# lab_1_zasetskiy_usb_spi.net
KiCad netlist of a schematic drawn in Altium Designer
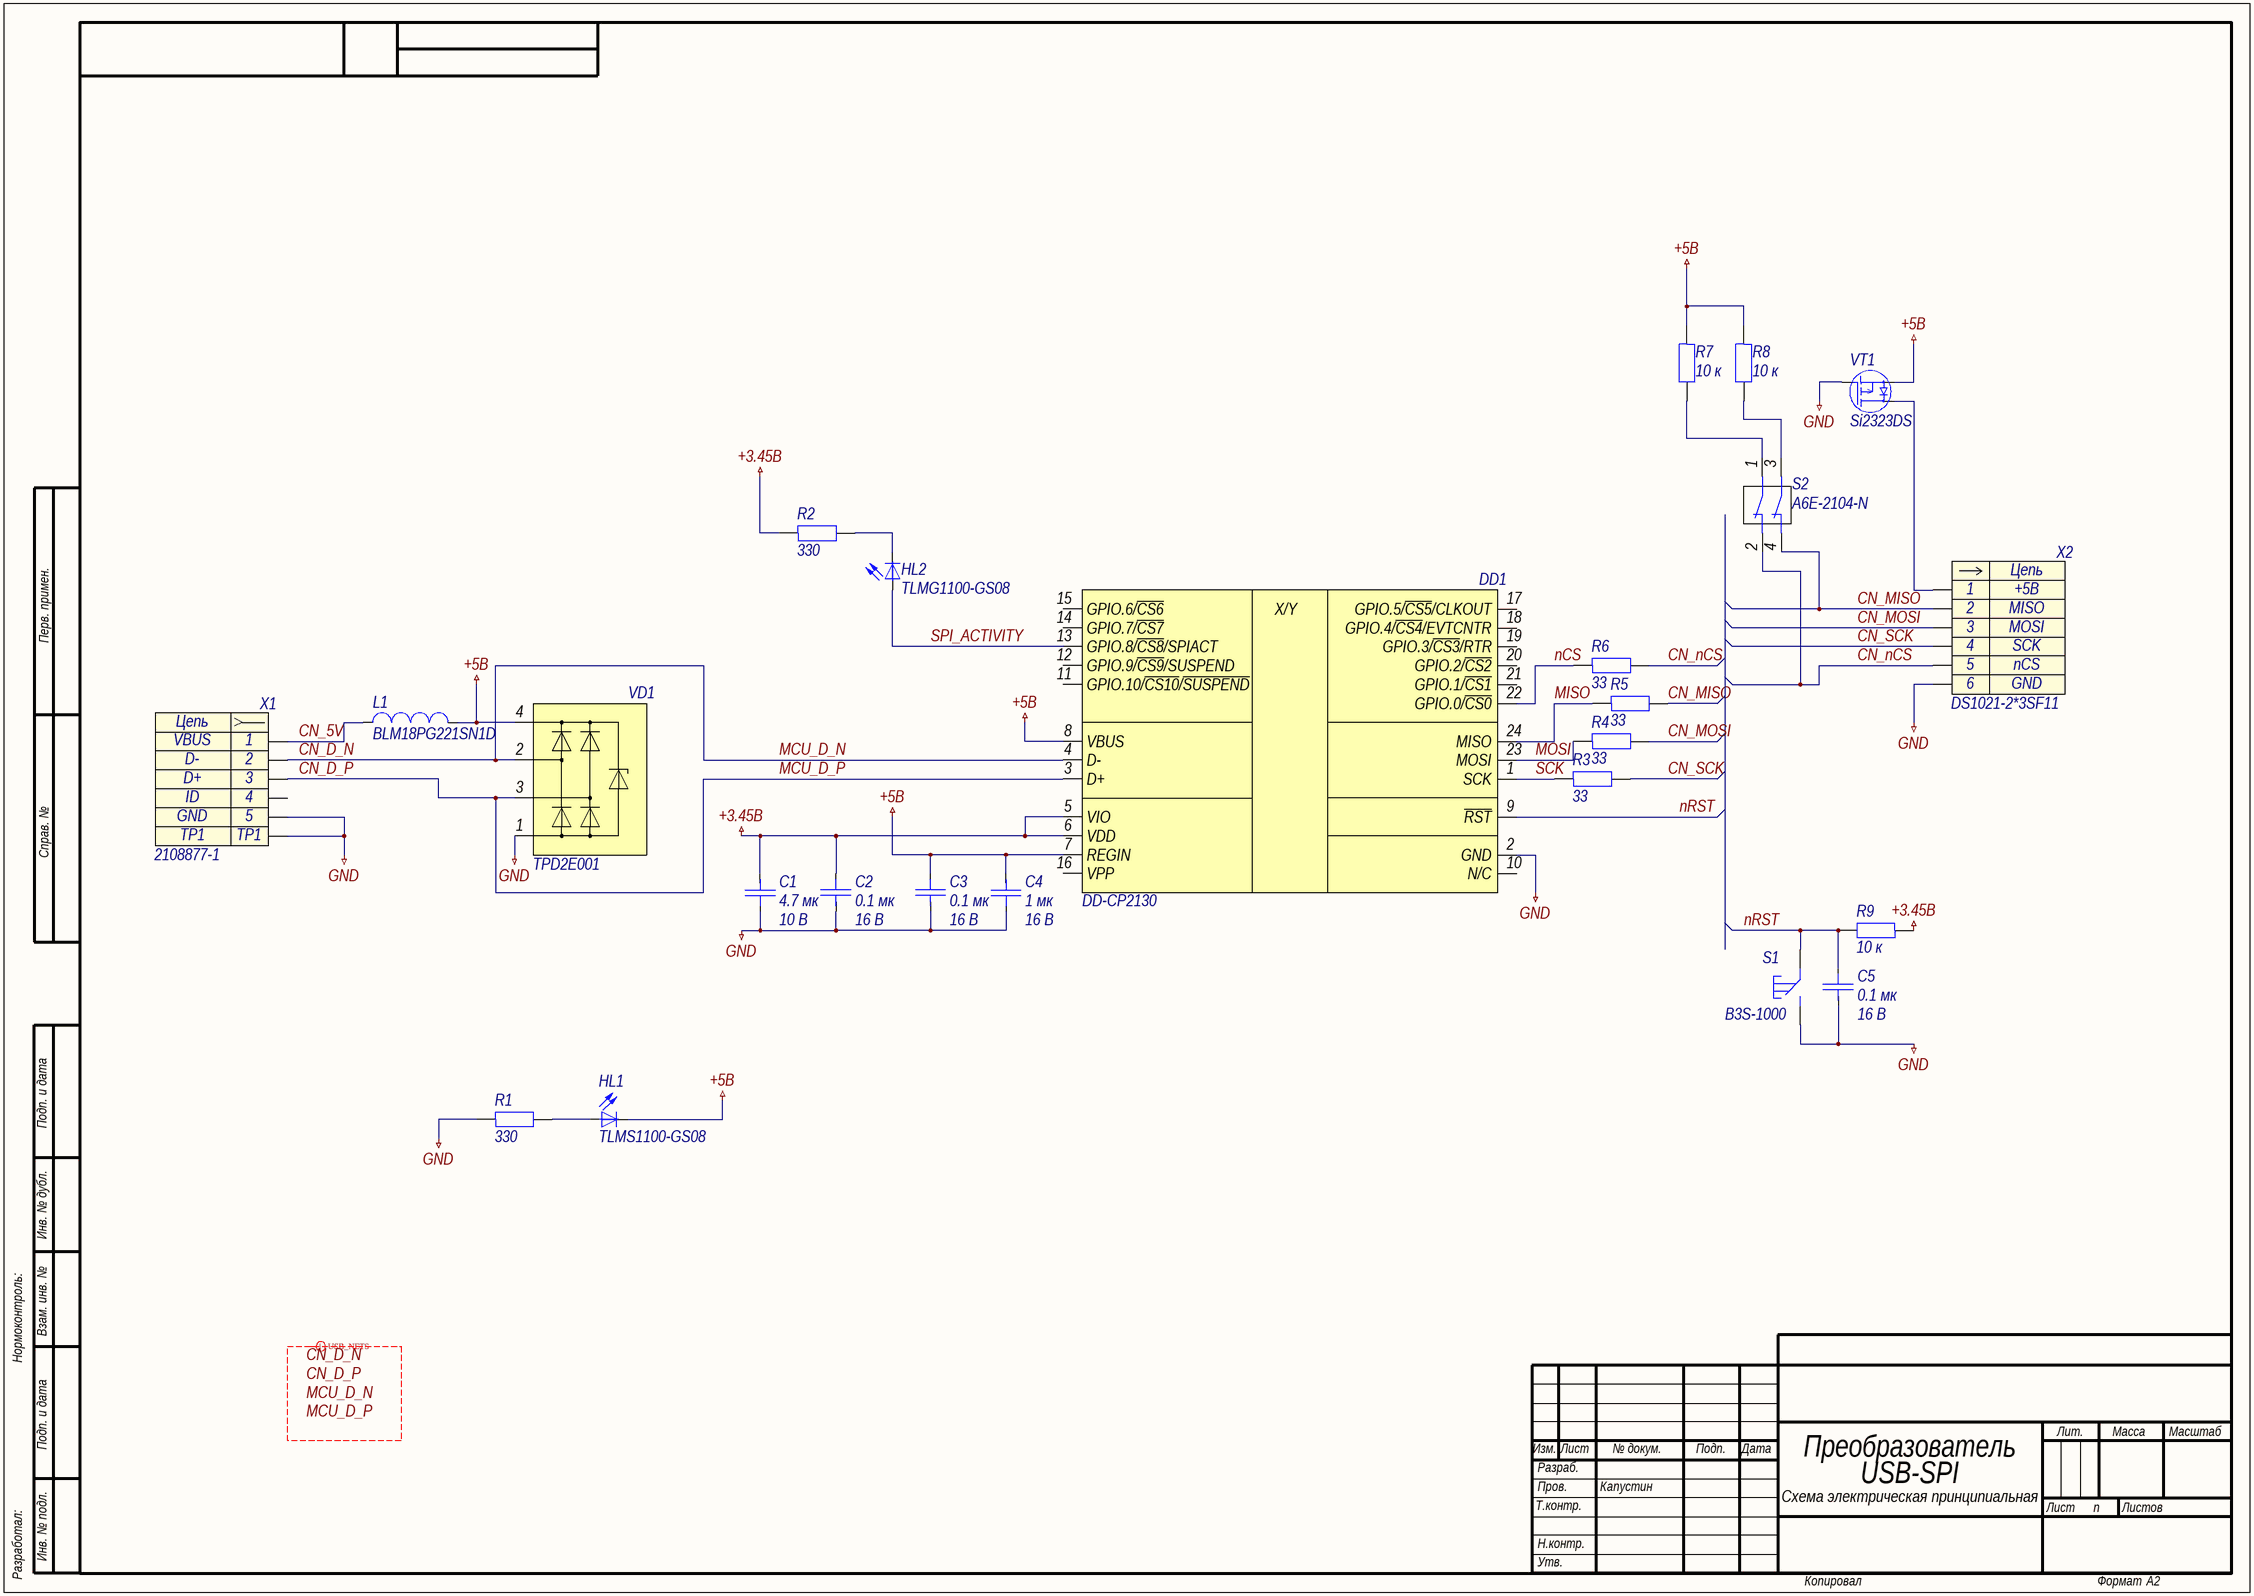
[diagram p0: lab_1_zasetskiy_usb_spi.SchDoc]

(export (version "E")
  (design (tool "Eeschema 10.0.6"))
  (components
    (comp (ref "C1")
      (value "4.7 мк")
      (footprint "C0402")
      (description "=Описание")
      (fields (field (name "НАПРЯЖЕНИЕ") "10 В"))
      (libsource (lib "Database_Students") (part "cap"))
    )
    (comp (ref "C2")
      (value "0.1 мк")
      (footprint "C0402")
      (description "=Описание")
      (fields (field (name "НАПРЯЖЕНИЕ") "16 В"))
      (libsource (lib "Database_Students") (part "cap"))
    )
    (comp (ref "C3")
      (value "0.1 мк")
      (footprint "C0402")
      (description "=Описание")
      (fields (field (name "НАПРЯЖЕНИЕ") "16 В"))
      (libsource (lib "Database_Students") (part "cap"))
    )
    (comp (ref "C4")
      (value "1 мк")
      (footprint "C0402")
      (description "=Описание")
      (fields (field (name "НАПРЯЖЕНИЕ") "16 В"))
      (libsource (lib "Database_Students") (part "cap"))
    )
    (comp (ref "C5")
      (value "0.1 мк")
      (footprint "C0402")
      (description "=Описание")
      (fields (field (name "НАПРЯЖЕНИЕ") "16 В"))
      (libsource (lib "Database_Students") (part "cap"))
    )
    (comp (ref "DD1")
      (value "DD-CP2130")
      (footprint "CP2130")
      (description "=Описание")
      (libsource (lib "Database_Students") (part "DD-CP2130"))
    )
    (comp (ref "HL1")
      (value "TLMS1100-GS08")
      (footprint "LED")
      (description "=Описание")
      (libsource (lib "Database_Students") (part "led"))
    )
    (comp (ref "HL2")
      (value "TLMG1100-GS08")
      (footprint "LED_GREEN")
      (description "=Описание")
      (libsource (lib "Database_Students") (part "led"))
    )
    (comp (ref "L1")
      (value "BLM18PG221SN1D")
      (footprint "L0603")
      (description "=Описание")
      (libsource (lib "Database_Students") (part "L-bead"))
    )
    (comp (ref "R1")
      (value "330")
      (footprint "R0603")
      (description "=Описание")
      (libsource (lib "Database_Students") (part "R-0.063W"))
    )
    (comp (ref "R2")
      (value "330")
      (footprint "R0603")
      (description "=Описание")
      (libsource (lib "Database_Students") (part "R-0.063W"))
    )
    (comp (ref "R3")
      (value "33")
      (footprint "R0603")
      (description "=Описание")
      (libsource (lib "Database_Students") (part "R-0.063W"))
    )
    (comp (ref "R4")
      (value "33")
      (footprint "R0603")
      (description "=Описание")
      (libsource (lib "Database_Students") (part "R-0.063W"))
    )
    (comp (ref "R5")
      (value "33")
      (footprint "R0603")
      (description "=Описание")
      (libsource (lib "Database_Students") (part "R-0.063W"))
    )
    (comp (ref "R6")
      (value "33")
      (footprint "R0603")
      (description "=Описание")
      (libsource (lib "Database_Students") (part "R-0.063W"))
    )
    (comp (ref "R7")
      (value "10 к")
      (footprint "R0603")
      (description "=Описание")
      (libsource (lib "Database_Students") (part "R-0.063W"))
    )
    (comp (ref "R8")
      (value "10 к")
      (footprint "R0603")
      (description "=Описание")
      (libsource (lib "Database_Students") (part "R-0.063W"))
    )
    (comp (ref "R9")
      (value "10 к")
      (footprint "R0603")
      (description "=Описание")
      (libsource (lib "Database_Students") (part "R-0.063W"))
    )
    (comp (ref "S1")
      (value "B3S-1000")
      (footprint "BUTTON")
      (description "=Описание")
      (libsource (lib "Database_Students") (part "S-button"))
    )
    (comp (ref "S2")
      (value "A6E-2104-N")
      (footprint "A6E-2104-N")
      (description "=Описание")
      (libsource (lib "Database_Students") (part "switch"))
    )
    (comp (ref "VD1")
      (value "TPD2E001")
      (footprint "SOP")
      (libsource (lib "Database_Students") (part "tpd2e001"))
    )
    (comp (ref "VT1")
      (value "Si2323DS")
      (footprint "VT-SOT23")
      (description "=Описание")
      (libsource (lib "Database_Students") (part "P-channel_MOSFET"))
    )
    (comp (ref "X1")
      (value "2108877-1")
      (footprint "2108877-1")
      (description "=Описание")
      (libsource (lib "Database_Students") (part "MICRO_USB-B"))
    )
    (comp (ref "X2")
      (value "DS1021-2*3SF11")
      (footprint "PLS_2.54_2x3")
      (description "=Описание")
      (libsource (lib "Database_Students") (part "DS1021-2*3SF11"))
    )
  )
  (nets
    (net (code "1") (name "+3.45В") (class "Default")
      (node (ref "C1") (pin "2") (pinfunction "2_2") (pintype "passive"))
      (node (ref "C2") (pin "1") (pinfunction "1_1") (pintype "passive"))
      (node (ref "DD1") (pin "5") (pinfunction "VIO_5") (pintype "passive"))
      (node (ref "DD1") (pin "6") (pinfunction "VDD_6") (pintype "passive"))
      (node (ref "R2") (pin "1") (pinfunction "1_1") (pintype "passive"))
      (node (ref "R9") (pin "1") (pinfunction "1_1") (pintype "passive"))
    )
    (net (code "2") (name "+5В") (class "Default")
      (node (ref "C3") (pin "1") (pinfunction "1_1") (pintype "passive"))
      (node (ref "C4") (pin "2") (pinfunction "2_2") (pintype "passive"))
      (node (ref "DD1") (pin "7") (pinfunction "REGIN_7") (pintype "passive"))
      (node (ref "DD1") (pin "8") (pinfunction "VBUS_8") (pintype "passive"))
      (node (ref "HL1") (pin "2") (pinfunction "K_2") (pintype "passive"))
      (node (ref "L1") (pin "2") (pinfunction "2_2") (pintype "passive"))
      (node (ref "R7") (pin "1") (pinfunction "1_1") (pintype "passive"))
      (node (ref "R8") (pin "1") (pinfunction "1_1") (pintype "passive"))
      (node (ref "VD1") (pin "4") (pintype "passive"))
      (node (ref "VT1") (pin "3") (pinfunction "3_3") (pintype "passive"))
    )
    (net (code "3") (name "/CN_5V") (class "Default")
      (node (ref "L1") (pin "1") (pinfunction "1_1") (pintype "passive"))
      (node (ref "X1") (pin "1") (pinfunction "1_1") (pintype "passive"))
    )
    (net (code "4") (name "/CN_D_N") (class "Default")
      (node (ref "DD1") (pin "4") (pinfunction "D-_4") (pintype "passive"))
      (node (ref "VD1") (pin "2") (pintype "passive"))
      (node (ref "X1") (pin "2") (pinfunction "2_2") (pintype "passive"))
    )
    (net (code "5") (name "/CN_D_P") (class "Default")
      (node (ref "DD1") (pin "3") (pinfunction "D+_3") (pintype "passive"))
      (node (ref "VD1") (pin "3") (pintype "passive"))
      (node (ref "X1") (pin "3") (pinfunction "3_3") (pintype "passive"))
    )
    (net (code "6") (name "/CN_MISO") (class "Default")
      (node (ref "R5") (pin "2") (pinfunction "2_2") (pintype "passive"))
      (node (ref "S2") (pin "4") (pinfunction "4_4") (pintype "passive"))
      (node (ref "X2") (pin "2") (pinfunction "2_2") (pintype "passive"))
    )
    (net (code "7") (name "/CN_MOSI") (class "Default")
      (node (ref "R4") (pin "2") (pinfunction "2_2") (pintype "passive"))
      (node (ref "X2") (pin "3") (pinfunction "3_3") (pintype "passive"))
    )
    (net (code "8") (name "/CN_SCK") (class "Default")
      (node (ref "R3") (pin "2") (pinfunction "2_2") (pintype "passive"))
      (node (ref "X2") (pin "4") (pinfunction "4_4") (pintype "passive"))
    )
    (net (code "9") (name "/CN_nCS") (class "Default")
      (node (ref "R6") (pin "2") (pinfunction "2_2") (pintype "passive"))
      (node (ref "S2") (pin "2") (pinfunction "2_2") (pintype "passive"))
      (node (ref "X2") (pin "5") (pinfunction "5_5") (pintype "passive"))
    )
    (net (code "10") (name "/MISO") (class "Default")
      (node (ref "DD1") (pin "24") (pinfunction "MISO_24") (pintype "passive"))
      (node (ref "R5") (pin "1") (pinfunction "1_1") (pintype "passive"))
    )
    (net (code "11") (name "/MOSI") (class "Default")
      (node (ref "DD1") (pin "23") (pinfunction "MOSI_23") (pintype "passive"))
      (node (ref "R4") (pin "1") (pinfunction "1_1") (pintype "passive"))
    )
    (net (code "12") (name "/SCK") (class "Default")
      (node (ref "DD1") (pin "1") (pinfunction "SCK_1") (pintype "passive"))
      (node (ref "R3") (pin "1") (pinfunction "1_1") (pintype "passive"))
    )
    (net (code "13") (name "/SPI_ACTIVITY") (class "Default")
      (node (ref "DD1") (pin "13") (pinfunction "GPIO.8/~{CS8}/SPIACT_13") (pintype "passive"))
      (node (ref "HL2") (pin "1") (pinfunction "A_1") (pintype "passive"))
    )
    (net (code "14") (name "/nCS") (class "Default")
      (node (ref "DD1") (pin "22") (pinfunction "GPIO.0/~{CS0}_22") (pintype "passive"))
      (node (ref "R6") (pin "1") (pinfunction "1_1") (pintype "passive"))
    )
    (net (code "15") (name "/nRST") (class "Default")
      (node (ref "C5") (pin "1") (pinfunction "1_1") (pintype "passive"))
      (node (ref "DD1") (pin "9") (pinfunction "~{RST}_9") (pintype "passive"))
      (node (ref "R9") (pin "2") (pinfunction "2_2") (pintype "passive"))
      (node (ref "S1") (pin "2") (pinfunction "2_2") (pintype "passive"))
    )
    (net (code "16") (name "GND") (class "Default")
      (node (ref "C1") (pin "1") (pinfunction "1_1") (pintype "passive"))
      (node (ref "C2") (pin "2") (pinfunction "2_2") (pintype "passive"))
      (node (ref "C3") (pin "2") (pinfunction "2_2") (pintype "passive"))
      (node (ref "C4") (pin "1") (pinfunction "1_1") (pintype "passive"))
      (node (ref "C5") (pin "2") (pinfunction "2_2") (pintype "passive"))
      (node (ref "DD1") (pin "2") (pinfunction "GND_2") (pintype "passive"))
      (node (ref "R1") (pin "1") (pinfunction "1_1") (pintype "passive"))
      (node (ref "VD1") (pin "1") (pintype "passive"))
      (node (ref "X1") (pin "5") (pinfunction "5_5") (pintype "passive"))
      (node (ref "X1") (pin "TP1") (pinfunction "TP1_TP1") (pintype "passive"))
      (node (ref "X2") (pin "6") (pinfunction "6_6") (pintype "passive"))
    )
    (net (code "17") (name "Net-(HL1-A)") (class "Default")
      (node (ref "HL1") (pin "1") (pinfunction "A_1") (pintype "passive"))
      (node (ref "R1") (pin "2") (pinfunction "2_2") (pintype "passive"))
    )
    (net (code "18") (name "Net-(HL2-K)") (class "Default")
      (node (ref "HL2") (pin "2") (pinfunction "K_2") (pintype "passive"))
      (node (ref "R2") (pin "2") (pinfunction "2_2") (pintype "passive"))
    )
    (net (code "19") (name "Net-(R7-Pad2)") (class "Default")
      (node (ref "R7") (pin "2") (pinfunction "2_2") (pintype "passive"))
      (node (ref "S2") (pin "1") (pinfunction "1_1") (pintype "passive"))
    )
    (net (code "20") (name "Net-(R8-Pad2)") (class "Default")
      (node (ref "R8") (pin "2") (pinfunction "2_2") (pintype "passive"))
      (node (ref "S2") (pin "3") (pinfunction "3_3") (pintype "passive"))
    )
    (net (code "21") (name "Net-(VT1-Pad2)") (class "Default")
      (node (ref "VT1") (pin "2") (pinfunction "2_2") (pintype "passive"))
      (node (ref "X2") (pin "1") (pinfunction "1_1") (pintype "passive"))
    )
    (net (code "22") (name "unconnected-(DD1-GPIO.1{slash}~{CS1}-Pad21)") (class "Default")
      (node (ref "DD1") (pin "21") (pinfunction "GPIO.1/~{CS1}_21") (pintype "passive"))
    )
    (net (code "23") (name "unconnected-(DD1-GPIO.2{slash}~{CS2}-Pad20)") (class "Default")
      (node (ref "DD1") (pin "20") (pinfunction "GPIO.2/~{CS2}_20") (pintype "passive"))
    )
    (net (code "24") (name "unconnected-(DD1-GPIO.3{slash}~{CS3}{slash}RTR-Pad19)") (class "Default")
      (node (ref "DD1") (pin "19") (pinfunction "GPIO.3/~{CS3}/RTR_19") (pintype "passive"))
    )
    (net (code "25") (name "unconnected-(DD1-GPIO.4{slash}~{CS4}{slash}EVTCNTR-Pad18)") (class "Default")
      (node (ref "DD1") (pin "18") (pinfunction "GPIO.4/~{CS4}/EVTCNTR_18") (pintype "passive"))
    )
    (net (code "26") (name "unconnected-(DD1-GPIO.5{slash}~{CS5}{slash}CLKOUT-Pad17)") (class "Default")
      (node (ref "DD1") (pin "17") (pinfunction "GPIO.5/~{CS5}/CLKOUT_17") (pintype "passive"))
    )
    (net (code "27") (name "unconnected-(DD1-GPIO.6{slash}~{CS6}-Pad15)") (class "Default")
      (node (ref "DD1") (pin "15") (pinfunction "GPIO.6/~{CS6}_15") (pintype "passive"))
    )
    (net (code "28") (name "unconnected-(DD1-GPIO.7{slash}~{CS7}-Pad14)") (class "Default")
      (node (ref "DD1") (pin "14") (pinfunction "GPIO.7/~{CS7}_14") (pintype "passive"))
    )
    (net (code "29") (name "unconnected-(DD1-GPIO.9{slash}~{CS9}{slash}SUSPEND-Pad12)") (class "Default")
      (node (ref "DD1") (pin "12") (pinfunction "GPIO.9/~{CS9}/SUSPEND_12") (pintype "passive"))
    )
    (net (code "30") (name "unconnected-(DD1-GPIO.10{slash}~{CS10}{slash}~{SUSPEND}-Pad11)") (class "Default")
      (node (ref "DD1") (pin "11") (pinfunction "GPIO.10/~{CS10}/~{SUSPEND}_11") (pintype "passive"))
    )
    (net (code "31") (name "unconnected-(DD1-N{slash}C-Pad10)") (class "Default")
      (node (ref "DD1") (pin "10") (pinfunction "N/C_10") (pintype "passive"))
    )
    (net (code "32") (name "unconnected-(DD1-VPP-Pad16)") (class "Default")
      (node (ref "DD1") (pin "16") (pinfunction "VPP_16") (pintype "passive"))
    )
    (net (code "33") (name "unconnected-(S1-Pad1)") (class "Default")
      (node (ref "S1") (pin "1") (pinfunction "1_1") (pintype "passive"))
    )
    (net (code "34") (name "unconnected-(VT1-Pad1)") (class "Default")
      (node (ref "VT1") (pin "1") (pinfunction "1_1") (pintype "passive"))
    )
    (net (code "35") (name "unconnected-(X1-Pad4)") (class "Default")
      (node (ref "X1") (pin "4") (pinfunction "4_4") (pintype "passive"))
    )
  )
)
